# voeding.net
KiCad netlist of a schematic drawn in Altium Designer
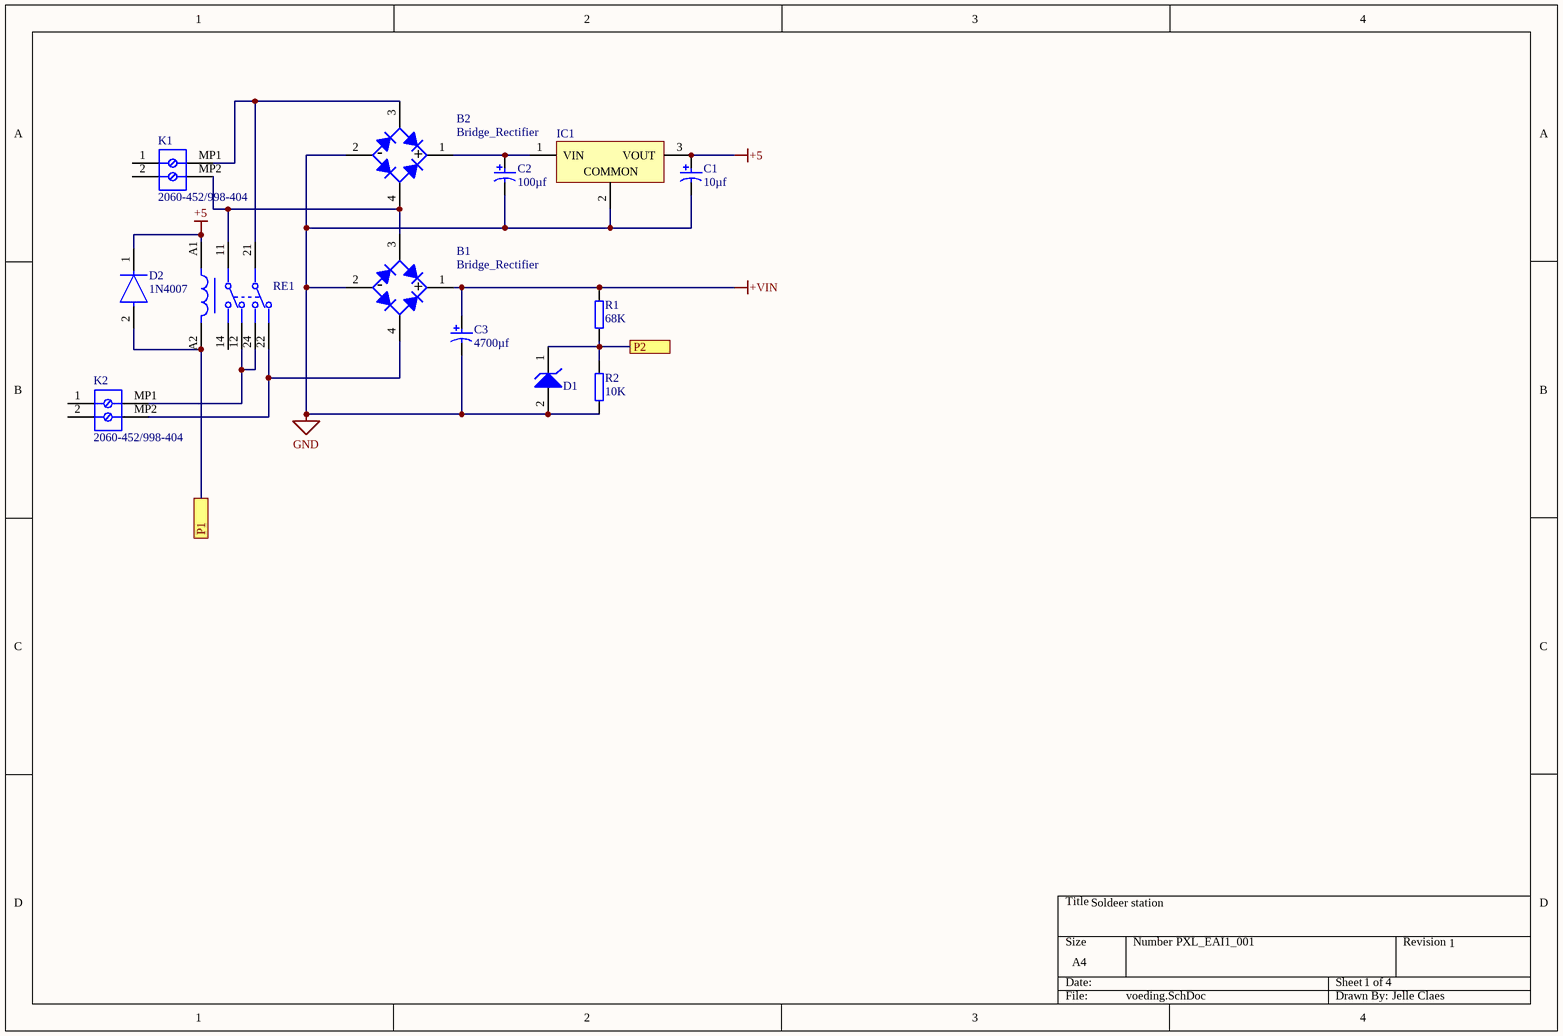
[diagram p0: voeding.SchDoc]

(export (version "E")
  (design (tool "Eeschema 10.0.6"))
  (components
    (comp (ref "B1")
      (value "Bridge_Rectifier")
      (footprint "ttf")
      (fields (field (name "MANUFACTURER") "Diodes Inc"))
      (libsource (lib "soldeerstation") (part "Bridge_Rectifier"))
    )
    (comp (ref "B2")
      (value "Bridge_Rectifier")
      (footprint "ttf")
      (fields (field (name "MANUFACTURER") "Diodes Inc"))
      (libsource (lib "soldeerstation") (part "Bridge_Rectifier"))
    )
    (comp (ref "C1")
      (value "10µf")
      (footprint "D4L5.4")
      (fields (field (name "MANUFACTURER") "Panasonic"))
      (libsource (lib "soldeerstation") (part "Capacitor_Electrolytic"))
    )
    (comp (ref "C2")
      (value "100µf")
      (footprint "CE_D8_L10")
      (fields (field (name "MANUFACTURER") "Panasonic"))
      (libsource (lib "soldeerstation") (part "Capacitor_Electrolytic"))
    )
    (comp (ref "C3")
      (value "4700µf")
      (footprint "CE_D25_L25_plugin")
      (fields (field (name "MANUFACTURER") "Panasonic"))
      (libsource (lib "soldeerstation") (part "Capacitor_Electrolytic"))
    )
    (comp (ref "D1")
      (value "Zener_Diode")
      (footprint "SOD-123FL")
      (fields (field (name "MANUFACTURER") "On Semiconductor") (field (name "PARTNUMBER") "1SMB5920BT3G"))
      (libsource (lib "soldeerstation") (part "Zener_Diode"))
    )
    (comp (ref "D2")
      (value "1N4007")
      (footprint "SOD-123FL")
      (fields
        (field (name "MANUFACTURER") "Diotec")
        (field (name "OCTOPART") "https://octopart.com/1n4007-diotec-4040411")
      )
      (libsource (lib "soldeerstation") (part "Diode"))
    )
    (comp (ref "IC1")
      (value "OKI-78SR-5/1.5-W36-C")
      (footprint "OKI78SR515W36C")
      (description "Non-Isolated DC/DC Converter, 7.5 W, 7 to 36 V, 1.5 A, -40 to 85 degC, 3-Pin THD, RoHS")
      (fields (field (name "MANUFACTURER") "Murata"))
      (libsource (lib "soldeerstation") (part "OKI-78SR-5/1.5-W36-C"))
    )
    (comp (ref "K1")
      (value "2060-452/998-404")
      (footprint "WAGO-2060-452_V")
      (description "Terminal Block, Pitch 4 mm, 1 x 2 Position, Height 4.5 mm, -60 to 105 degC, RoHS, Tape and Reel")
      (fields (field (name "MANUFACTURER") "WAGO"))
      (libsource (lib "soldeerstation") (part "WAGO-2060"))
    )
    (comp (ref "K2")
      (value "2060-452/998-404")
      (footprint "WAGO-2060-452_V")
      (description "Terminal Block, Pitch 4 mm, 1 x 2 Position, Height 4.5 mm, -60 to 105 degC, RoHS, Tape and Reel")
      (fields (field (name "MANUFACTURER") "WAGO"))
      (libsource (lib "soldeerstation") (part "WAGO-2060"))
    )
    (comp (ref "R1")
      (value "68K")
      (footprint "R_0805_M")
      (fields (field (name "MANUFACTURER") "Vishay Dale") (field (name "PART NUMBER") "CRCW08050000Z0EA"))
      (libsource (lib "soldeerstation") (part "Resistor"))
    )
    (comp (ref "R2")
      (value "10K")
      (footprint "R_0805_M")
      (fields (field (name "MANUFACTURER") "Vishay Dale") (field (name "PART NUMBER") "CRCW08050000Z0EA"))
      (libsource (lib "soldeerstation") (part "Resistor"))
    )
    (comp (ref "RE1")
      (value "RELAY_GENERAL_PURPOSE")
      (footprint "RT42")
      (fields
        (field (name "MANUFACTURER PART NUMBER") "RT424005")
        (field (name "OCTOPART") "https://octopart.com/5-1393243-9-te+connectivity-41835766")
        (field (name "MANUFACTURER") "TE Connectivity")
      )
      (libsource (lib "soldeerstation") (part "RELAY_GENERAL_PURPOSE"))
    )
  )
  (nets
    (net (code "1") (name "+5") (class "Default")
      (node (ref "C1") (pin "2") (pinfunction "2_2") (pintype "passive"))
      (node (ref "D2") (pin "1") (pinfunction "C_1") (pintype "passive"))
      (node (ref "IC1") (pin "3") (pinfunction "VOUT_3") (pintype "power_in"))
      (node (ref "RE1") (pin "A1") (pinfunction "A1_A1") (pintype "passive"))
    )
    (net (code "2") (name "+VIN") (class "Default")
      (node (ref "B1") (pin "1") (pinfunction "K_1") (pintype "passive"))
      (node (ref "C3") (pin "2") (pinfunction "2_2") (pintype "passive"))
      (node (ref "R1") (pin "2") (pinfunction "2_2") (pintype "passive"))
    )
    (net (code "3") (name "/P1") (class "Default")
      (node (ref "D2") (pin "2") (pinfunction "A_2") (pintype "passive"))
      (node (ref "RE1") (pin "A2") (pinfunction "A2_A2") (pintype "passive"))
    )
    (net (code "4") (name "/P2") (class "Default")
      (node (ref "D1") (pin "1") (pinfunction "K_1") (pintype "passive"))
      (node (ref "R1") (pin "1") (pinfunction "1_1") (pintype "passive"))
      (node (ref "R2") (pin "2") (pinfunction "2_2") (pintype "passive"))
    )
    (net (code "5") (name "GND") (class "Default")
      (node (ref "B1") (pin "2") (pinfunction "A_2") (pintype "passive"))
      (node (ref "B2") (pin "2") (pinfunction "A_2") (pintype "passive"))
      (node (ref "C1") (pin "1") (pinfunction "1_1") (pintype "passive"))
      (node (ref "C2") (pin "1") (pinfunction "1_1") (pintype "passive"))
      (node (ref "C3") (pin "1") (pinfunction "1_1") (pintype "passive"))
      (node (ref "D1") (pin "2") (pinfunction "A_2") (pintype "passive"))
      (node (ref "IC1") (pin "2") (pinfunction "COMMON_2") (pintype "power_in"))
      (node (ref "R2") (pin "1") (pinfunction "1_1") (pintype "passive"))
    )
    (net (code "6") (name "Net-(B1-C-Pad3)") (class "Default")
      (node (ref "B1") (pin "3") (pinfunction "C_3") (pintype "passive"))
      (node (ref "B2") (pin "4") (pinfunction "C_4") (pintype "passive"))
      (node (ref "K1") (pin "MP2") (pinfunction "MP2_MP2") (pintype "passive"))
      (node (ref "RE1") (pin "11") (pinfunction "11_11") (pintype "passive"))
    )
    (net (code "7") (name "Net-(B1-C-Pad4)") (class "Default")
      (node (ref "B1") (pin "4") (pinfunction "C_4") (pintype "passive"))
      (node (ref "K2") (pin "MP2") (pinfunction "MP2_MP2") (pintype "passive"))
      (node (ref "RE1") (pin "22") (pinfunction "22_22") (pintype "passive"))
    )
    (net (code "8") (name "Net-(B2-C-Pad3)") (class "Default")
      (node (ref "B2") (pin "3") (pinfunction "C_3") (pintype "passive"))
      (node (ref "K1") (pin "MP1") (pinfunction "MP1_MP1") (pintype "passive"))
      (node (ref "RE1") (pin "21") (pinfunction "21_21") (pintype "passive"))
    )
    (net (code "9") (name "Net-(B2-K)") (class "Default")
      (node (ref "B2") (pin "1") (pinfunction "K_1") (pintype "passive"))
      (node (ref "C2") (pin "2") (pinfunction "2_2") (pintype "passive"))
      (node (ref "IC1") (pin "1") (pinfunction "VIN_1") (pintype "power_in"))
    )
    (net (code "10") (name "Net-(K2-PadMP1)") (class "Default")
      (node (ref "K2") (pin "MP1") (pinfunction "MP1_MP1") (pintype "passive"))
      (node (ref "RE1") (pin "12") (pinfunction "12_12") (pintype "passive"))
      (node (ref "RE1") (pin "24") (pinfunction "24_24") (pintype "passive"))
    )
    (net (code "11") (name "unconnected-(K1-Pad1)") (class "Default")
      (node (ref "K1") (pin "1") (pinfunction "1_1") (pintype "passive"))
    )
    (net (code "12") (name "unconnected-(K1-Pad2)") (class "Default")
      (node (ref "K1") (pin "2") (pinfunction "2_2") (pintype "passive"))
    )
    (net (code "13") (name "unconnected-(K2-Pad1)") (class "Default")
      (node (ref "K2") (pin "1") (pinfunction "1_1") (pintype "passive"))
    )
    (net (code "14") (name "unconnected-(K2-Pad2)") (class "Default")
      (node (ref "K2") (pin "2") (pinfunction "2_2") (pintype "passive"))
    )
    (net (code "15") (name "unconnected-(RE1-Pad14)") (class "Default")
      (node (ref "RE1") (pin "14") (pinfunction "14_14") (pintype "passive"))
    )
  )
)
